# 03_POWER.net
KiCad netlist of a schematic drawn in Altium Designer
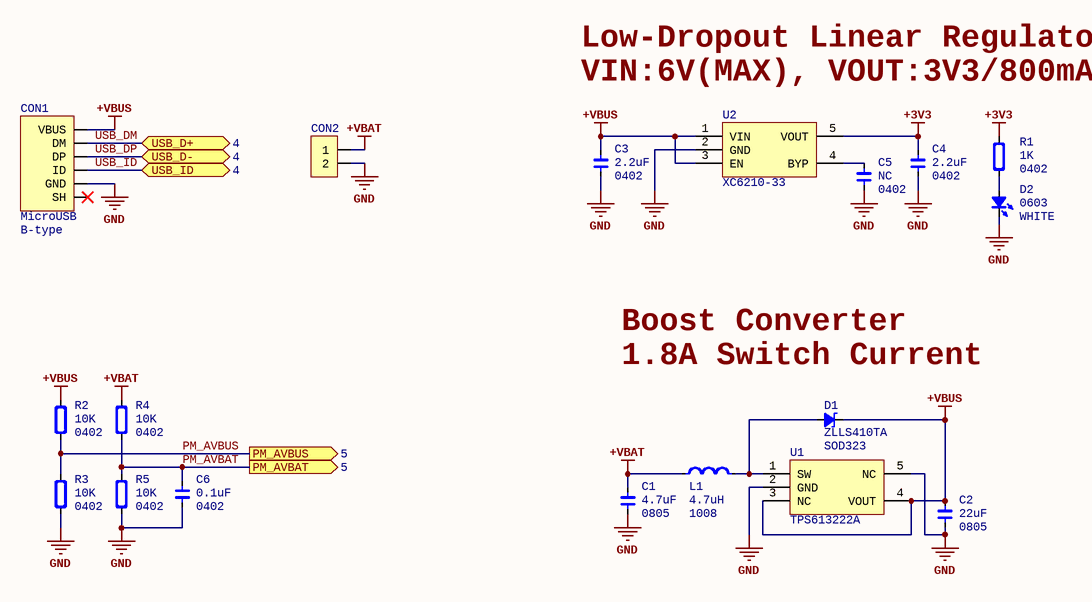
[diagram p0: [03] POWER.SchDoc]

(export (version "E")
  (design (tool "Eeschema 10.0.6"))
  (components
    (comp (ref "C1")
      (value "4.7uF")
      (footprint "PCB_PassiveCap:CAP_0805")
      (description "Capacitor")
      (fields (field (name "TYPE") "0805") (field (name "Comment") "C0805"))
      (libsource (lib "SCH_Passive") (part "Cap_0805"))
    )
    (comp (ref "C2")
      (value "22uF")
      (footprint "PCB_PassiveCap:CAP_0805")
      (description "Capacitor")
      (fields (field (name "TYPE") "0805") (field (name "Comment") "C0805"))
      (libsource (lib "SCH_Passive") (part "Cap_0805"))
    )
    (comp (ref "C3")
      (value "2.2uF")
      (footprint "PCB_PassiveCap:CAP_0402")
      (description "Capacitor")
      (fields (field (name "TYPE") "0402") (field (name "Comment") "C0402"))
      (libsource (lib "SCH_Passive") (part "Cap_0402"))
    )
    (comp (ref "C4")
      (value "2.2uF")
      (footprint "PCB_PassiveCap:CAP_0402")
      (description "Capacitor")
      (fields (field (name "TYPE") "0402") (field (name "Comment") "C0402"))
      (libsource (lib "SCH_Passive") (part "Cap_0402"))
    )
    (comp (ref "C5")
      (value "NC")
      (footprint "PCB_PassiveCap:CAP_0402")
      (description "Capacitor")
      (fields (field (name "TYPE") "0402") (field (name "Comment") "C0402"))
      (libsource (lib "SCH_Passive") (part "Cap_0402"))
    )
    (comp (ref "C6")
      (value "0.1uF")
      (footprint "PCB_PassiveCap:CAP_0402")
      (description "Capacitor")
      (fields (field (name "TYPE") "0402") (field (name "Comment") "C0402"))
      (libsource (lib "SCH_Passive") (part "Cap_0402"))
    )
    (comp (ref "CON1")
      (value "MicroUSB")
      (footprint "PCB_USB:USB_Micro-AB")
      (description "USB")
      (fields (field (name "TYPE") "B-type"))
      (libsource (lib "SCH_USB") (part "USB_Micro"))
    )
    (comp (ref "CON2")
      (value "MX1.25_2P")
      (footprint "PCB_Connector:MX1.25_S90_2P")
      (description "MX")
      (libsource (lib "SCH_Connector") (part "MX1.25_2P"))
    )
    (comp (ref "D1")
      (value "ZLLS410TA")
      (footprint "PCB_ActiveDIO:SOD-323")
      (description "Schottky Diode")
      (fields (field (name "TYPE") "SOD323"))
      (libsource (lib "SCH_Active") (part "SchottkyDiode_SOD323"))
    )
    (comp (ref "D2")
      (value "WHITE")
      (footprint "PCB_ActiveLED:LED_0603_YELLOW")
      (description "LED")
      (fields (field (name "TYPE") "0603"))
      (libsource (lib "SCH_Active") (part "LED_0603"))
    )
    (comp (ref "L1")
      (value "4.7uH")
      (footprint "PCB_PassiveInd:IND_1008")
      (description "Inductor")
      (fields (field (name "TYPE") "1008") (field (name "Comment") "H1008"))
      (libsource (lib "SCH_Passive") (part "Ind_1008"))
    )
    (comp (ref "R1")
      (value "1K")
      (footprint "PCB_PassiveRes:RES_0402")
      (description "Resistor")
      (fields (field (name "TYPE") "0402") (field (name "Comment") "R0402"))
      (libsource (lib "SCH_Passive") (part "Res_0402"))
    )
    (comp (ref "R2")
      (value "10K")
      (footprint "PCB_PassiveRes:RES_0402")
      (description "Resistor")
      (fields (field (name "TYPE") "0402") (field (name "Comment") "R0402"))
      (libsource (lib "SCH_Passive") (part "Res_0402"))
    )
    (comp (ref "R3")
      (value "10K")
      (footprint "PCB_PassiveRes:RES_0402")
      (description "Resistor")
      (fields (field (name "TYPE") "0402") (field (name "Comment") "R0402"))
      (libsource (lib "SCH_Passive") (part "Res_0402"))
    )
    (comp (ref "R4")
      (value "10K")
      (footprint "PCB_PassiveRes:RES_0402")
      (description "Resistor")
      (fields (field (name "TYPE") "0402") (field (name "Comment") "R0402"))
      (libsource (lib "SCH_Passive") (part "Res_0402"))
    )
    (comp (ref "R5")
      (value "10K")
      (footprint "PCB_PassiveRes:RES_0402")
      (description "Resistor")
      (fields (field (name "TYPE") "0402") (field (name "Comment") "R0402"))
      (libsource (lib "SCH_Passive") (part "Res_0402"))
    )
    (comp (ref "U1")
      (value "TPS613222A")
      (footprint "PCB_IntegratedCircuit:SOT23-5")
      (description "Power")
      (libsource (lib "SCH_IntegratedCircuit") (part "TPS61322xx"))
    )
    (comp (ref "U2")
      (value "XC6210-33")
      (footprint "PCB_IntegratedCircuit:SOT23-5")
      (description "Power")
      (libsource (lib "SCH_IntegratedCircuit") (part "RT9193"))
    )
  )
  (nets
    (net (code "1") (name "+3V3") (class "Default")
      (node (ref "C4") (pin "2") (pinfunction "2_2") (pintype "passive"))
      (node (ref "R1") (pin "2") (pinfunction "2_2") (pintype "passive"))
      (node (ref "U2") (pin "5") (pinfunction "VOUT_5") (pintype "passive"))
    )
    (net (code "2") (name "+VBAT") (class "Default")
      (node (ref "C1") (pin "2") (pinfunction "2_2") (pintype "passive"))
      (node (ref "CON2") (pin "1") (pinfunction "1_1") (pintype "passive"))
      (node (ref "L1") (pin "1") (pinfunction "1_1") (pintype "passive"))
      (node (ref "R4") (pin "2") (pinfunction "2_2") (pintype "passive"))
    )
    (net (code "3") (name "+VBUS") (class "Default")
      (node (ref "C2") (pin "2") (pinfunction "2_2") (pintype "passive"))
      (node (ref "C3") (pin "2") (pinfunction "2_2") (pintype "passive"))
      (node (ref "CON1") (pin "1") (pinfunction "VBUS_1") (pintype "passive"))
      (node (ref "D1") (pin "2") (pinfunction "K_2") (pintype "passive"))
      (node (ref "R2") (pin "2") (pinfunction "2_2") (pintype "passive"))
      (node (ref "U1") (pin "3") (pinfunction "NC_3") (pintype "passive"))
      (node (ref "U1") (pin "4") (pinfunction "VOUT_4") (pintype "passive"))
      (node (ref "U2") (pin "1") (pinfunction "VIN_1") (pintype "passive"))
      (node (ref "U2") (pin "3") (pinfunction "EN_3") (pintype "power_in"))
    )
    (net (code "4") (name "/PM_AVBAT") (class "Default")
      (node (ref "C6") (pin "2") (pinfunction "2_2") (pintype "passive"))
      (node (ref "R4") (pin "1") (pinfunction "1_1") (pintype "passive"))
      (node (ref "R5") (pin "2") (pinfunction "2_2") (pintype "passive"))
    )
    (net (code "5") (name "/PM_AVBUS") (class "Default")
      (node (ref "R2") (pin "1") (pinfunction "1_1") (pintype "passive"))
      (node (ref "R3") (pin "2") (pinfunction "2_2") (pintype "passive"))
    )
    (net (code "6") (name "/USB_DM") (class "Default")
      (node (ref "CON1") (pin "2") (pinfunction "DM_2") (pintype "passive"))
    )
    (net (code "7") (name "/USB_DP") (class "Default")
      (node (ref "CON1") (pin "3") (pinfunction "DP_3") (pintype "passive"))
    )
    (net (code "8") (name "/USB_ID") (class "Default")
      (node (ref "CON1") (pin "4") (pinfunction "ID_4") (pintype "passive"))
    )
    (net (code "9") (name "GND") (class "Default")
      (node (ref "C1") (pin "1") (pinfunction "1_1") (pintype "passive"))
      (node (ref "C2") (pin "1") (pinfunction "1_1") (pintype "passive"))
      (node (ref "C3") (pin "1") (pinfunction "1_1") (pintype "passive"))
      (node (ref "C4") (pin "1") (pinfunction "1_1") (pintype "passive"))
      (node (ref "C5") (pin "1") (pinfunction "1_1") (pintype "passive"))
      (node (ref "C6") (pin "1") (pinfunction "1_1") (pintype "passive"))
      (node (ref "CON1") (pin "5") (pinfunction "GND_5") (pintype "passive"))
      (node (ref "CON2") (pin "2") (pinfunction "2_2") (pintype "passive"))
      (node (ref "D2") (pin "2") (pinfunction "K_2") (pintype "passive"))
      (node (ref "R3") (pin "1") (pinfunction "1_1") (pintype "passive"))
      (node (ref "R5") (pin "1") (pinfunction "1_1") (pintype "passive"))
      (node (ref "U1") (pin "2") (pinfunction "GND_2") (pintype "passive"))
      (node (ref "U1") (pin "5") (pinfunction "NC_5") (pintype "passive"))
      (node (ref "U2") (pin "2") (pinfunction "GND_2") (pintype "passive"))
    )
    (net (code "10") (name "Net-(D1-A)") (class "Default")
      (node (ref "D1") (pin "1") (pinfunction "A_1") (pintype "passive"))
      (node (ref "L1") (pin "2") (pinfunction "2_2") (pintype "passive"))
      (node (ref "U1") (pin "1") (pinfunction "SW_1") (pintype "passive"))
    )
    (net (code "11") (name "Net-(D2-A)") (class "Default")
      (node (ref "D2") (pin "1") (pinfunction "A_1") (pintype "passive"))
      (node (ref "R1") (pin "1") (pinfunction "1_1") (pintype "passive"))
    )
    (net (code "12") (name "Net-(U2-BYP)") (class "Default")
      (node (ref "C5") (pin "2") (pinfunction "2_2") (pintype "passive"))
      (node (ref "U2") (pin "4") (pinfunction "BYP_4") (pintype "passive"))
    )
    (net (code "13") (name "unconnected-(CON1-SH-Pad0)") (class "Default")
      (node (ref "CON1") (pin "0") (pinfunction "SH_0") (pintype "passive+no_connect"))
    )
  )
)
